# ATmega324PB_Xplained_Pro_Target_MCU.net
KiCad netlist of a schematic drawn in Altium Designer
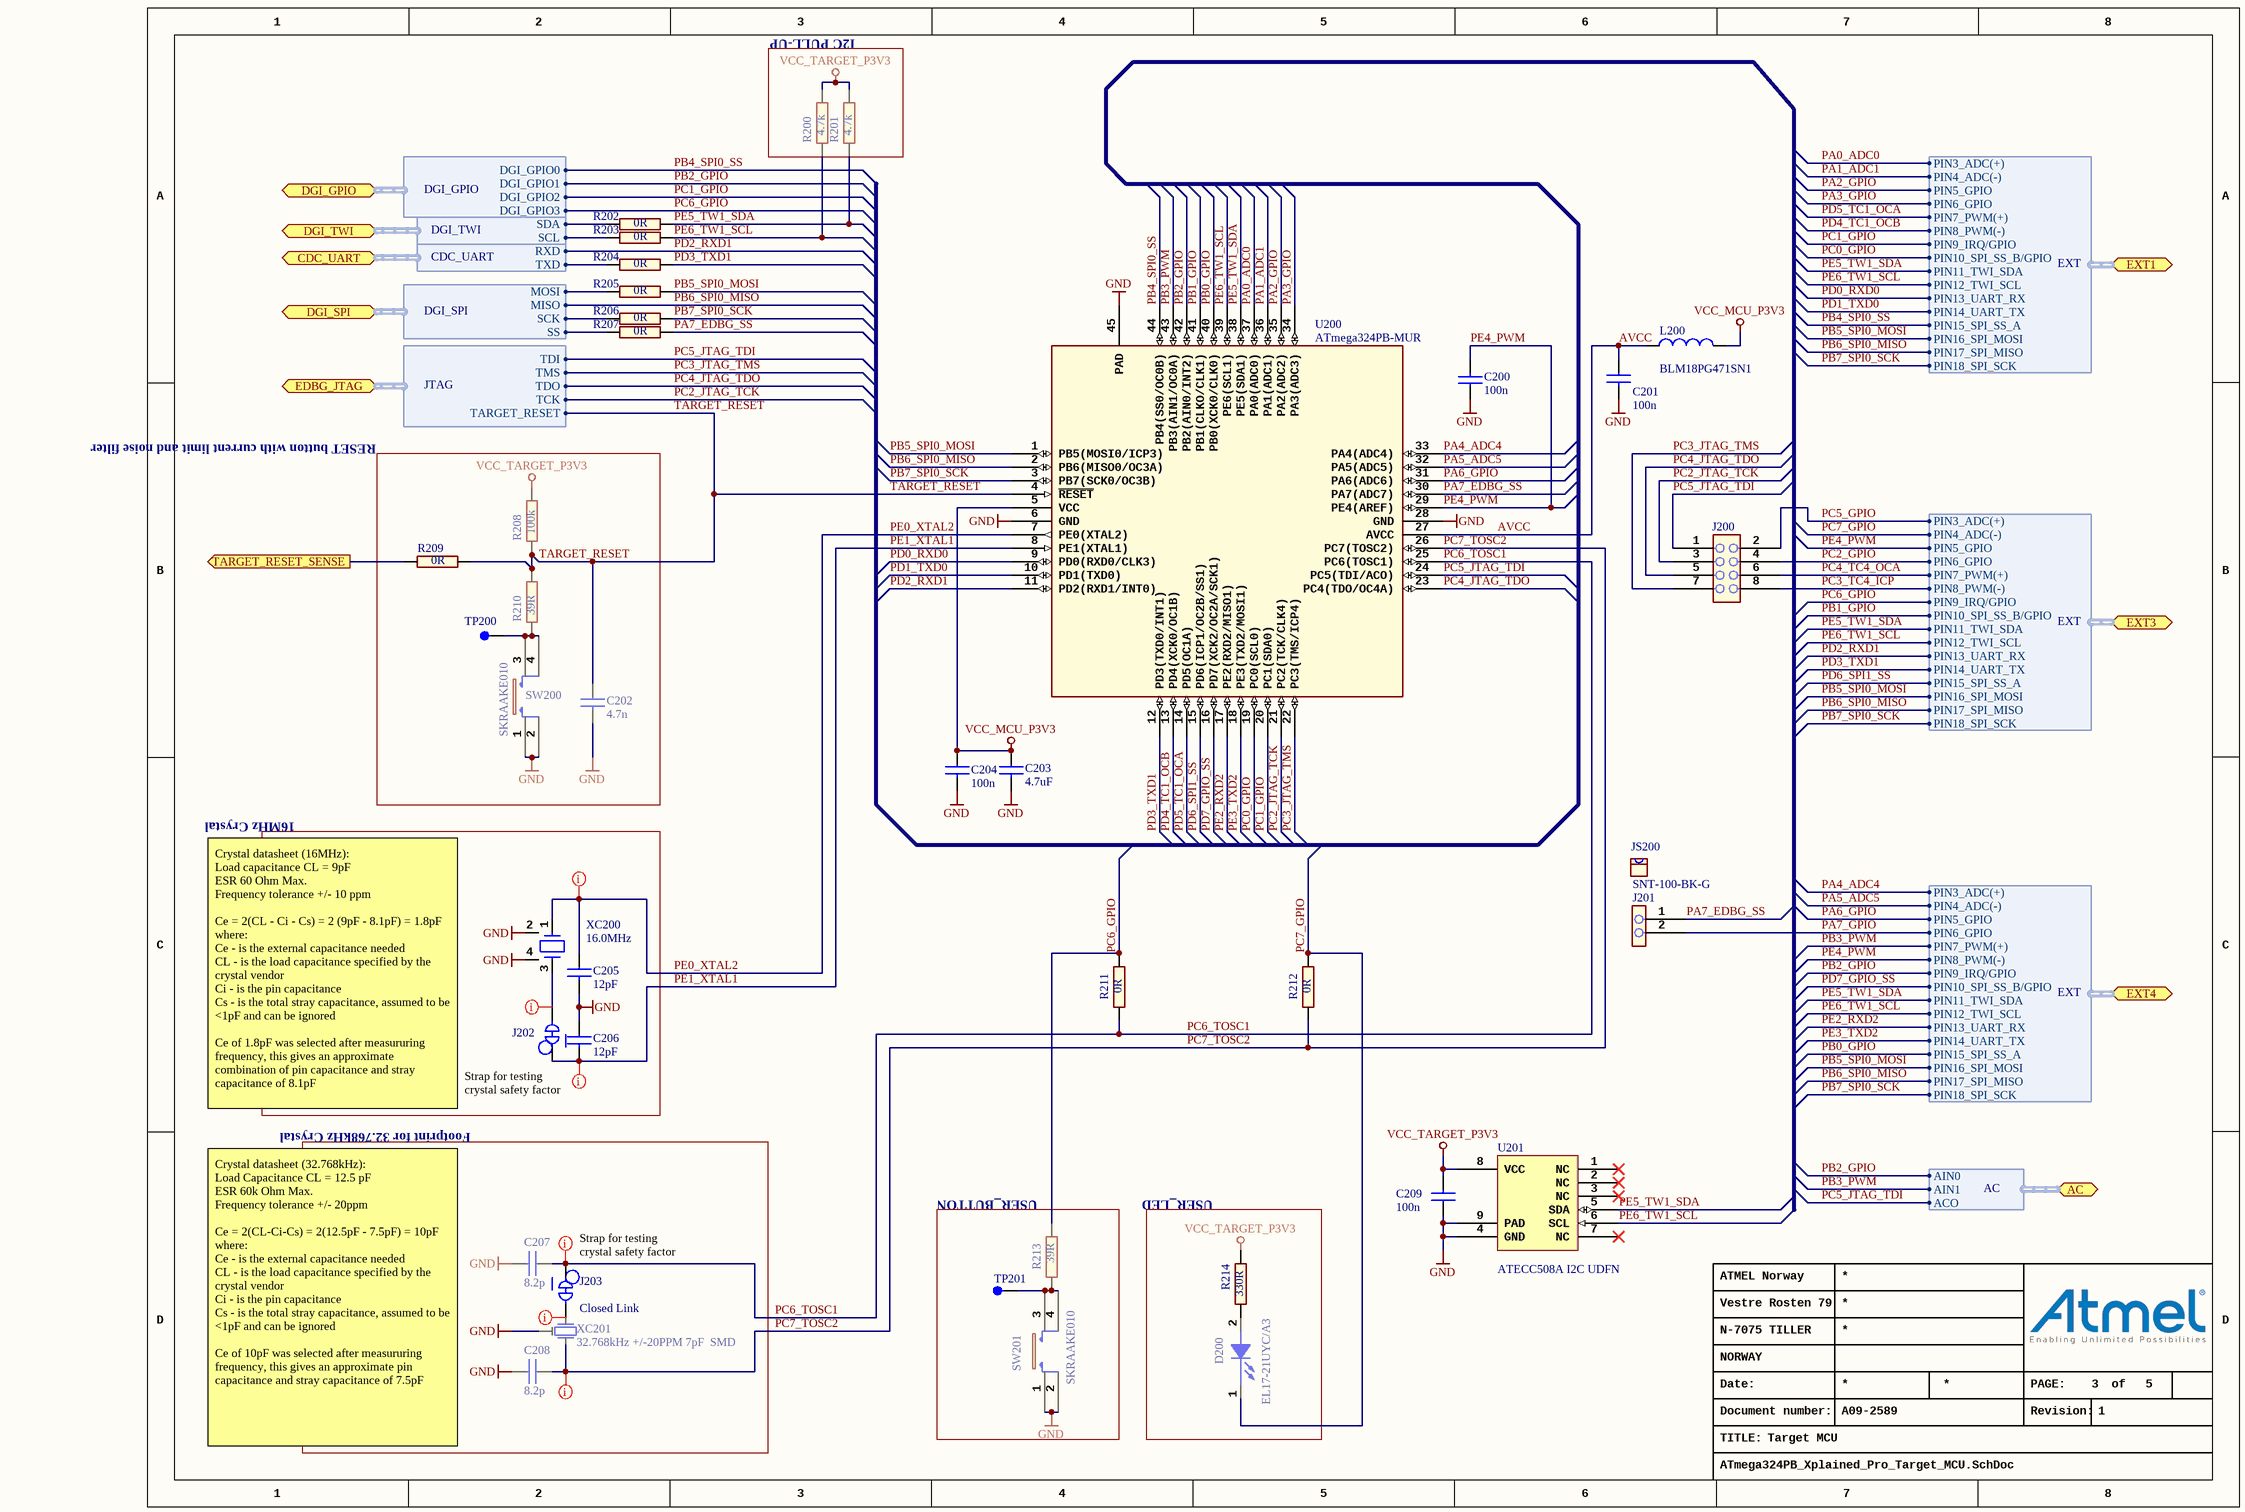
[diagram p0: ATmega324PB_Xplained_Pro_Target_MCU.SchDoc]

(export (version "E")
  (design (tool "Eeschema 10.0.6"))
  (components
    (comp (ref "C200")
      (value "100n")
      (footprint "AP1-00001")
      (description "Ceramic capacitor, SMD 0402, X7R, 16V, +/-10%")
      (fields (field (name "TOLERANCE") "16V, +/-10%") (field (name "MANUFACTURER") "Kemet"))
      (libsource (lib "AltiumDbLib") (part "CAP-NONPOL"))
    )
    (comp (ref "C201")
      (value "100n")
      (footprint "AP1-00001")
      (description "Ceramic capacitor, SMD 0402, X7R, 16V, +/-10%")
      (fields (field (name "TOLERANCE") "16V, +/-10%") (field (name "MANUFACTURER") "Kemet"))
      (libsource (lib "AltiumDbLib") (part "CAP-NONPOL"))
    )
    (comp (ref "C202")
      (value "4.7n")
      (footprint "AP1-00053")
      (description "Ceramic capacitor, SMD 0402, X7R, 25V, +/-10% (de35287)")
      (fields (field (name "TOLERANCE") "25V, +/-10%"))
      (libsource (lib "AltiumDbLib") (part "CAP-NONPOL"))
    )
    (comp (ref "C203")
      (value "4.7uF")
      (footprint "AP1-00039")
      (description "Ceramic capacitor, SMD 0603, X5R, 10V, 10% (de31036)")
      (fields (field (name "MANUFACTURER") "tdk") (field (name "MPN") "C1608X5R1A475K"))
      (libsource (lib "AltiumDbLib") (part "CAP-NONPOL"))
    )
    (comp (ref "C204")
      (value "100n")
      (footprint "AP1-00001")
      (description "Ceramic capacitor, SMD 0402, X7R, 16V, +/-10%")
      (fields (field (name "TOLERANCE") "16V, +/-10%") (field (name "MANUFACTURER") "Kemet"))
      (libsource (lib "AltiumDbLib") (part "CAP-NONPOL"))
    )
    (comp (ref "C205")
      (value "12pF")
      (footprint "AP1-00038")
      (description "Ceramic capacitor, SMD 0402, NP0, 50V, +/-5% (de19819)")
      (fields (field (name "TOLERANCE") "5%") (field (name "MANUFACTURER") "Kyocera-elco"))
      (libsource (lib "AltiumDbLib") (part "CAP-NONPOL"))
    )
    (comp (ref "C206")
      (value "12pF")
      (footprint "AP1-00038")
      (description "Ceramic capacitor, SMD 0402, NP0, 50V, +/-5% (de19819)")
      (fields (field (name "TOLERANCE") "5%") (field (name "MANUFACTURER") "Kyocera-elco"))
      (libsource (lib "AltiumDbLib") (part "CAP-NONPOL"))
    )
    (comp (ref "C207")
      (value "8.2p")
      (footprint "AP1-00001")
      (description "Ceramic capacitor, SMD 0402, NP0, 50V, +/-5%")
      (fields (field (name "TOLERANCE") "50V, +/-5%"))
      (libsource (lib "AltiumDbLib") (part "CAP-NONPOL"))
    )
    (comp (ref "C208")
      (value "8.2p")
      (footprint "AP1-00001")
      (description "Ceramic capacitor, SMD 0402, NP0, 50V, +/-5%")
      (fields (field (name "TOLERANCE") "50V, +/-5%"))
      (libsource (lib "AltiumDbLib") (part "CAP-NONPOL"))
    )
    (comp (ref "C209")
      (value "100n")
      (footprint "AP1-00001")
      (description "Ceramic capacitor, SMD 0402, X7R, 16V, +/-10%")
      (fields (field (name "TOLERANCE") "16V, +/-10%") (field (name "MANUFACTURER") "Kemet"))
      (libsource (lib "AltiumDbLib") (part "CAP-NONPOL"))
    )
    (comp (ref "D200")
      (value "EL17-21UYC/A3")
      (footprint "AP4-00013")
      (description "LED, Yellow, Wave length=591nm, SMD 0805, ±70°")
      (fields (field (name "MANUFACTURER") "Everlight") (field (name "MPN") "17-21UYC/S530-A3/TR8"))
      (libsource (lib "AltiumDbLib") (part "LED_12"))
    )
    (comp (ref "J200")
      (value "~")
      (footprint "AP8-00971")
      (description "2x4 pin header, 2.54 mm pitch, Pin-in-Paste THM")
      (fields (field (name "MANUFACTURER") "SAMTEC") (field (name "MPN") "HMTSW-104-23-F-D-237"))
      (libsource (lib "AltiumDbLib") (part "HEADER 2x4"))
    )
    (comp (ref "J201")
      (value "~")
      (footprint "AP8-00733")
      (description "1x2 pin header, 2.54mm pitch, Pin-in-Paste THM")
      (fields (field (name "MANUFACTURER") "SAMTEC") (field (name "MPN") "HMTSW-102-23-F-S-237"))
      (libsource (lib "AltiumDbLib") (part "HEADER 1x2"))
    )
    (comp (ref "J202")
      (value "~")
      (footprint "AP8-00595")
      (description "Closed Link 0402")
      (libsource (lib "AltiumDbLib") (part "SMD-STRAP_CLOSED"))
    )
    (comp (ref "J203")
      (value "Closed Link")
      (footprint "AP8-00595")
      (description "Closed Link 0402")
      (libsource (lib "AltiumDbLib") (part "SMD-STRAP_CLOSED"))
    )
    (comp (ref "JS200")
      (value "SNT-100-BK-G")
      (footprint "AP8-00525")
      (description "Jumper cap for 2.54mm pinheader")
      (fields (field (name "MANUFACTURER") "SAMTEC"))
      (libsource (lib "AltiumDbLib") (part "JUMPER_CAP"))
    )
    (comp (ref "L200")
      (value "BLM18PG471SN1")
      (footprint "AP3-00005")
      (description "SMD RF inductor 0603. Z=470Ohm (@100MHz), Max R(dc)=0.65Ohm, Max current=1A")
      (fields (field (name "TOLERANCE") "±25%") (field (name "MANUFACTURER") "Murata"))
      (libsource (lib "AltiumDbLib") (part "INDUCTOR"))
    )
    (comp (ref "R200")
      (value "4.7k")
      (footprint "AP2-00000")
      (description "Thick film resistor, SMD 0402, 1/16W, 1%")
      (fields (field (name "TOLERANCE") "1 %"))
      (libsource (lib "") (part "R2_1"))
    )
    (comp (ref "R201")
      (value "4.7k")
      (footprint "AP2-00000")
      (description "Thick film resistor, SMD 0402, 1/16W, 1%")
      (fields (field (name "TOLERANCE") "1 %"))
      (libsource (lib "") (part "R2_1"))
    )
    (comp (ref "R202")
      (value "0R")
      (footprint "AP2-00000")
      (description "RES 0.0 OHM 1/16W 0402 SMD")
      (fields (field (name "TOLERANCE") "1 %") (field (name "MANUFACTURER") "(n/a)"))
      (libsource (lib "AltiumDbLib") (part "R2"))
    )
    (comp (ref "R203")
      (value "0R")
      (footprint "AP2-00000")
      (description "RES 0.0 OHM 1/16W 0402 SMD")
      (fields (field (name "TOLERANCE") "1 %") (field (name "MANUFACTURER") "(n/a)"))
      (libsource (lib "AltiumDbLib") (part "R2"))
    )
    (comp (ref "R204")
      (value "0R")
      (footprint "AP2-00000")
      (description "RES 0.0 OHM 1/16W 0402 SMD")
      (fields (field (name "TOLERANCE") "1 %") (field (name "MANUFACTURER") "(n/a)"))
      (libsource (lib "AltiumDbLib") (part "R2"))
    )
    (comp (ref "R205")
      (value "0R")
      (footprint "AP2-00000")
      (description "RES 0.0 OHM 1/16W 0402 SMD")
      (fields (field (name "TOLERANCE") "1 %") (field (name "MANUFACTURER") "(n/a)"))
      (libsource (lib "AltiumDbLib") (part "R2"))
    )
    (comp (ref "R206")
      (value "0R")
      (footprint "AP2-00000")
      (description "RES 0.0 OHM 1/16W 0402 SMD")
      (fields (field (name "TOLERANCE") "1 %") (field (name "MANUFACTURER") "(n/a)"))
      (libsource (lib "AltiumDbLib") (part "R2"))
    )
    (comp (ref "R207")
      (value "0R")
      (footprint "AP2-00000")
      (description "RES 0.0 OHM 1/16W 0402 SMD")
      (fields (field (name "TOLERANCE") "1 %") (field (name "MANUFACTURER") "(n/a)"))
      (libsource (lib "AltiumDbLib") (part "R2"))
    )
    (comp (ref "R208")
      (value "100k")
      (footprint "AP2-00011")
      (description "Thick film resistor, SMD 0402, 1/16W, 1%")
      (fields (field (name "TOLERANCE") "1 %"))
      (libsource (lib "") (part "R2_1"))
    )
    (comp (ref "R209")
      (value "0R")
      (footprint "AP2-00000")
      (description "RES 0.0 OHM 1/16W 0402 SMD")
      (fields (field (name "TOLERANCE") "1 %") (field (name "MANUFACTURER") "(n/a)"))
      (libsource (lib "AltiumDbLib") (part "R2"))
    )
    (comp (ref "R210")
      (value "39R")
      (footprint "AP2-00011")
      (description "Thick film resistor, SMD 0402, 1/16W, 1%")
      (fields (field (name "TOLERANCE") "1 %"))
      (libsource (lib "") (part "R2_2"))
    )
    (comp (ref "R211")
      (value "0R")
      (footprint "AP2-00000")
      (description "RES 0.0 OHM 1/16W 0402 SMD")
      (fields (field (name "TOLERANCE") "1 %") (field (name "MANUFACTURER") "(n/a)"))
      (libsource (lib "") (part "R2_1"))
    )
    (comp (ref "R212")
      (value "0R")
      (footprint "AP2-00000")
      (description "RES 0.0 OHM 1/16W 0402 SMD")
      (fields (field (name "TOLERANCE") "1 %") (field (name "MANUFACTURER") "(n/a)"))
      (libsource (lib "") (part "R2_1"))
    )
    (comp (ref "R213")
      (value "39R")
      (footprint "AP2-00011")
      (description "Thick film resistor, SMD 0402, 1/16W, 1%")
      (fields (field (name "TOLERANCE") "1 %"))
      (libsource (lib "") (part "R2_2"))
    )
    (comp (ref "R214")
      (value "330R")
      (footprint "AP2-00000")
      (description "Thick film resistor, SMD 0402, 1/16W, 1%")
      (fields (field (name "TOLERANCE") "1 %"))
      (libsource (lib "") (part "R2_1"))
    )
    (comp (ref "SW200")
      (value "SKRAAKE010")
      (footprint "AP8-00137")
      (description "6.2x6.2 mm SMD tact switch, same as A08-0091 but less force is needed")
      (fields
        (field (name "MANUFACTURER") "ALPS")
        (field (name "Comment") "Can be ordered in low volumes from Mouser")
      )
      (libsource (lib "AltiumDbLib") (part "PUSHBUTTON1"))
    )
    (comp (ref "SW201")
      (value "SKRAAKE010")
      (footprint "AP8-00137")
      (description "6.2x6.2 mm SMD tact switch, same as A08-0091 but less force is needed")
      (fields
        (field (name "MANUFACTURER") "ALPS")
        (field (name "Comment") "Can be ordered in low volumes from Mouser")
      )
      (libsource (lib "AltiumDbLib") (part "PUSHBUTTON1"))
    )
    (comp (ref "TP200")
      (value "~")
      (footprint "AP8-00010")
      (description "Single SMD testpad")
      (libsource (lib "AltiumDbLib") (part "TESTPOINT"))
    )
    (comp (ref "TP201")
      (value "~")
      (footprint "AP8-00010")
      (description "Single SMD testpad")
      (libsource (lib "AltiumDbLib") (part "TESTPOINT"))
    )
    (comp (ref "U200")
      (value "ATmega324PB-MUR")
      (footprint "AP6-00147")
      (description "AVR 8-bit RISC MCU")
      (fields
        (field (name "MANUFACTURER") "ATMEL")
        (field (name "Comment") "Footprint has tight silkscreen to solder mask expansion clearance")
      )
      (libsource (lib "AltiumDbLib") (part "ATmega324PB"))
    )
    (comp (ref "U201")
      (value "ATECC508A I2C UDFN")
      (footprint "AP6-00409")
      (description "ATECC508A with an I2C Interface and a 8 Pin UDFN Package with Paddle")
      (fields (field (name "MANUFACTURER") "ATMEL") (field (name "MPN") "ATECC508A-MAHDA-T"))
      (libsource (lib "AltiumDbLib") (part "ATECC508A_I2C_UDFN"))
    )
    (comp (ref "XC200")
      (value "16.0MHz")
      (footprint "AP7-00061")
      (description "16MHz uXtal, 3.2 x 2.5 mm SMD, CL=9pF, 15PPM, ESR=80ohm(Max.")
      (fields (field (name "TOLERANCE") "15ppm") (field (name "MANUFACTURER") "Epson Toyocom"))
      (libsource (lib "AltiumDbLib") (part "TSX-3225"))
    )
    (comp (ref "XC201")
      (value "32.768kHz +/-20PPM 7pF  SMD")
      (footprint "AP7-00044")
      (description "32k768 crystal, +-20ppm, CL=7pF, max ESR 60kOhm, SMD")
      (fields (field (name "TOLERANCE") "+/- 20 PPM") (field (name "MANUFACTURER") "Micro Crystal"))
      (libsource (lib "AltiumDbLib") (part "CRYSTAL_2P_metal"))
    )
  )
  (nets
    (net (code "7") (name "/AVCC") (class "Default")
      (node (ref "C201") (pin "1") (pinfunction "1_1") (pintype "passive"))
      (node (ref "L200") (pin "1") (pinfunction "1_1") (pintype "passive"))
      (node (ref "U200") (pin "27") (pinfunction "AVCC_27") (pintype "power_in"))
    )
    (net (code "9") (name "/MOSI") (class "Default")
      (node (ref "R205") (pin "1") (pinfunction "1_1") (pintype "passive"))
    )
    (net (code "10") (name "/PA0_ADC0") (class "Default")
      (node (ref "U200") (pin "37") (pinfunction "PA0(ADC0)_37") (pintype "bidirectional"))
    )
    (net (code "11") (name "/PA1_ADC1") (class "Default")
      (node (ref "U200") (pin "36") (pinfunction "PA1(ADC1)_36") (pintype "bidirectional"))
    )
    (net (code "12") (name "/PA2_GPIO") (class "Default")
      (node (ref "U200") (pin "35") (pinfunction "PA2(ADC2)_35") (pintype "bidirectional"))
    )
    (net (code "13") (name "/PA3_GPIO") (class "Default")
      (node (ref "U200") (pin "34") (pinfunction "PA3(ADC3)_34") (pintype "bidirectional"))
    )
    (net (code "14") (name "/PA4_ADC4") (class "Default")
      (node (ref "U200") (pin "33") (pinfunction "PA4(ADC4)_33") (pintype "bidirectional"))
    )
    (net (code "15") (name "/PA5_ADC5") (class "Default")
      (node (ref "U200") (pin "32") (pinfunction "PA5(ADC5)_32") (pintype "bidirectional"))
    )
    (net (code "16") (name "/PA6_GPIO") (class "Default")
      (node (ref "U200") (pin "31") (pinfunction "PA6(ADC6)_31") (pintype "bidirectional"))
    )
    (net (code "17") (name "/PA7_EDBG_SS") (class "Default")
      (node (ref "J201") (pin "1") (pinfunction "1_1") (pintype "passive"))
      (node (ref "R207") (pin "2") (pinfunction "2_2") (pintype "passive"))
      (node (ref "U200") (pin "30") (pinfunction "PA7(ADC7)_30") (pintype "bidirectional"))
    )
    (net (code "18") (name "/PA7_GPIO") (class "Default")
      (node (ref "J201") (pin "2") (pinfunction "2_2") (pintype "passive"))
    )
    (net (code "19") (name "/PB0_GPIO") (class "Default")
      (node (ref "U200") (pin "40") (pinfunction "PB0(XCK0/CLK0)_40") (pintype "bidirectional"))
    )
    (net (code "20") (name "/PB1_GPIO") (class "Default")
      (node (ref "U200") (pin "41") (pinfunction "PB1(CLKO/CLK1)_41") (pintype "bidirectional"))
    )
    (net (code "21") (name "/PB2_GPIO") (class "Default")
      (node (ref "U200") (pin "42") (pinfunction "PB2(AIN0/INT2)_42") (pintype "bidirectional"))
    )
    (net (code "22") (name "/PB3_PWM") (class "Default")
      (node (ref "U200") (pin "43") (pinfunction "PB3(AIN1/OC0A)_43") (pintype "bidirectional"))
    )
    (net (code "23") (name "/PB4_SPI0_SS") (class "Default")
      (node (ref "U200") (pin "44") (pinfunction "PB4(SS0/OC0B)_44") (pintype "bidirectional"))
    )
    (net (code "24") (name "/PB5_SPI0_MOSI") (class "Default")
      (node (ref "R205") (pin "2") (pinfunction "2_2") (pintype "passive"))
      (node (ref "U200") (pin "1") (pinfunction "PB5(MOSI0/ICP3)_1") (pintype "bidirectional"))
    )
    (net (code "25") (name "/PB6_SPI0_MISO") (class "Default")
      (node (ref "U200") (pin "2") (pinfunction "PB6(MISO0/OC3A)_2") (pintype "bidirectional"))
    )
    (net (code "26") (name "/PB7_SPI0_SCK") (class "Default")
      (node (ref "R206") (pin "2") (pinfunction "2_2") (pintype "passive"))
      (node (ref "U200") (pin "3") (pinfunction "PB7(SCK0/OC3B)_3") (pintype "bidirectional"))
    )
    (net (code "27") (name "/PC0_GPIO") (class "Default")
      (node (ref "U200") (pin "19") (pinfunction "PC0(SCL0)_19") (pintype "bidirectional"))
    )
    (net (code "28") (name "/PC1_GPIO") (class "Default")
      (node (ref "U200") (pin "20") (pinfunction "PC1(SDA0)_20") (pintype "bidirectional"))
    )
    (net (code "29") (name "/PC2_GPIO") (class "Default")
      (node (ref "J200") (pin "4") (pinfunction "4_4") (pintype "passive"))
    )
    (net (code "30") (name "/PC2_JTAG_TCK") (class "Default")
      (node (ref "J200") (pin "3") (pinfunction "3_3") (pintype "passive"))
      (node (ref "U200") (pin "21") (pinfunction "PC2(TCK/CLK4)_21") (pintype "bidirectional"))
    )
    (net (code "31") (name "/PC3_JTAG_TMS") (class "Default")
      (node (ref "J200") (pin "7") (pinfunction "7_7") (pintype "passive"))
      (node (ref "U200") (pin "22") (pinfunction "PC3(TMS/ICP4)_22") (pintype "bidirectional"))
    )
    (net (code "32") (name "/PC3_TC4_ICP") (class "Default")
      (node (ref "J200") (pin "8") (pinfunction "8_8") (pintype "passive"))
    )
    (net (code "33") (name "/PC4_JTAG_TDO") (class "Default")
      (node (ref "J200") (pin "5") (pinfunction "5_5") (pintype "passive"))
      (node (ref "U200") (pin "23") (pinfunction "PC4(TDO/OC4A)_23") (pintype "bidirectional"))
    )
    (net (code "34") (name "/PC4_TC4_OCA") (class "Default")
      (node (ref "J200") (pin "6") (pinfunction "6_6") (pintype "passive"))
    )
    (net (code "35") (name "/PC5_GPIO") (class "Default")
      (node (ref "J200") (pin "2") (pinfunction "2_2") (pintype "passive"))
    )
    (net (code "36") (name "/PC5_JTAG_TDI") (class "Default")
      (node (ref "J200") (pin "1") (pinfunction "1_1") (pintype "passive"))
      (node (ref "U200") (pin "24") (pinfunction "PC5(TDI/ACO)_24") (pintype "bidirectional"))
    )
    (net (code "37") (name "/PC6_GPIO") (class "Default")
      (node (ref "R211") (pin "2") (pinfunction "2_2") (pintype "passive"))
      (node (ref "R213") (pin "2") (pinfunction "2_2") (pintype "passive"))
    )
    (net (code "38") (name "/PC6_TOSC1") (class "Default")
      (node (ref "C207") (pin "1") (pinfunction "1_1") (pintype "passive"))
      (node (ref "J203") (pin "1") (pinfunction "1_1") (pintype "passive"))
      (node (ref "R211") (pin "1") (pinfunction "1_1") (pintype "passive"))
      (node (ref "U200") (pin "25") (pinfunction "PC6(TOSC1)_25") (pintype "bidirectional"))
    )
    (net (code "39") (name "/PC7_GPIO") (class "Default")
      (node (ref "D200") (pin "1") (pinfunction "CATHODE_1") (pintype "passive"))
      (node (ref "R212") (pin "2") (pinfunction "2_2") (pintype "passive"))
    )
    (net (code "40") (name "/PC7_TOSC2") (class "Default")
      (node (ref "C208") (pin "1") (pinfunction "1_1") (pintype "passive"))
      (node (ref "R212") (pin "1") (pinfunction "1_1") (pintype "passive"))
      (node (ref "U200") (pin "26") (pinfunction "PC7(TOSC2)_26") (pintype "bidirectional"))
      (node (ref "XC201") (pin "1") (pinfunction "1_1") (pintype "passive"))
    )
    (net (code "41") (name "/PD0_RXD0") (class "Default")
      (node (ref "U200") (pin "9") (pinfunction "PD0(RXD0/CLK3)_9") (pintype "bidirectional"))
    )
    (net (code "42") (name "/PD1_TXD0") (class "Default")
      (node (ref "U200") (pin "10") (pinfunction "PD1(TXD0)_10") (pintype "bidirectional"))
    )
    (net (code "43") (name "/PD2_RXD1") (class "Default")
      (node (ref "U200") (pin "11") (pinfunction "PD2(RXD1/INT0)_11") (pintype "bidirectional"))
    )
    (net (code "44") (name "/PD3_TXD1") (class "Default")
      (node (ref "R204") (pin "2") (pinfunction "2_2") (pintype "passive"))
      (node (ref "U200") (pin "12") (pinfunction "PD3(TXD0/INT1)_12") (pintype "bidirectional"))
    )
    (net (code "45") (name "/PD4_TC1_OCB") (class "Default")
      (node (ref "U200") (pin "13") (pinfunction "PD4(XCK0/OC1B)_13") (pintype "bidirectional"))
    )
    (net (code "46") (name "/PD5_TC1_OCA") (class "Default")
      (node (ref "U200") (pin "14") (pinfunction "PD5(OC1A)_14") (pintype "bidirectional"))
    )
    (net (code "47") (name "/PD6_SPI1_SS") (class "Default")
      (node (ref "U200") (pin "15") (pinfunction "PD6(ICP1/OC2B/SS1)_15") (pintype "bidirectional"))
    )
    (net (code "48") (name "/PD7_GPIO_SS") (class "Default")
      (node (ref "U200") (pin "16") (pinfunction "PD7(XCK2/OC2A/SCK1)_16") (pintype "bidirectional"))
    )
    (net (code "49") (name "/PE0_XTAL2") (class "Default")
      (node (ref "C205") (pin "1") (pinfunction "1_1") (pintype "passive"))
      (node (ref "U200") (pin "7") (pinfunction "PE0(XTAL2)_7") (pintype "output"))
      (node (ref "XC200") (pin "1") (pinfunction "IN_1") (pintype "passive"))
    )
    (net (code "50") (name "/PE1_XTAL1") (class "Default")
      (node (ref "C206") (pin "2") (pinfunction "2_2") (pintype "passive"))
      (node (ref "J202") (pin "1") (pinfunction "1_1") (pintype "passive"))
      (node (ref "U200") (pin "8") (pinfunction "PE1(XTAL1)_8") (pintype "input"))
    )
    (net (code "51") (name "/PE2_RXD2") (class "Default")
      (node (ref "U200") (pin "17") (pinfunction "PE2(RXD2/MISO1)_17") (pintype "bidirectional"))
    )
    (net (code "52") (name "/PE3_TXD2") (class "Default")
      (node (ref "U200") (pin "18") (pinfunction "PE3(TXD2/MOSI1)_18") (pintype "bidirectional"))
    )
    (net (code "53") (name "/PE4_PWM") (class "Default")
      (node (ref "C200") (pin "2") (pinfunction "2_2") (pintype "passive"))
      (node (ref "U200") (pin "29") (pinfunction "PE4(AREF)_29") (pintype "bidirectional"))
    )
    (net (code "54") (name "/PE5_TW1_SDA") (class "Default")
      (node (ref "R201") (pin "1") (pinfunction "1_1") (pintype "passive"))
      (node (ref "R202") (pin "2") (pinfunction "2_2") (pintype "passive"))
      (node (ref "U200") (pin "38") (pinfunction "PE5(SDA1)_38") (pintype "bidirectional"))
      (node (ref "U201") (pin "5") (pinfunction "SDA_5") (pintype "bidirectional"))
    )
    (net (code "55") (name "/PE6_TW1_SCL") (class "Default")
      (node (ref "R200") (pin "1") (pinfunction "1_1") (pintype "passive"))
      (node (ref "R203") (pin "2") (pinfunction "2_2") (pintype "passive"))
      (node (ref "U200") (pin "39") (pinfunction "PE6(SCL1)_39") (pintype "bidirectional"))
      (node (ref "U201") (pin "6") (pinfunction "SCL_6") (pintype "input"))
    )
    (net (code "56") (name "/SCK") (class "Default")
      (node (ref "R206") (pin "1") (pinfunction "1_1") (pintype "passive"))
    )
    (net (code "57") (name "/SCL") (class "Default")
      (node (ref "R203") (pin "1") (pinfunction "1_1") (pintype "passive"))
    )
    (net (code "58") (name "/SDA") (class "Default")
      (node (ref "R202") (pin "1") (pinfunction "1_1") (pintype "passive"))
    )
    (net (code "59") (name "/SS") (class "Default")
      (node (ref "R207") (pin "1") (pinfunction "1_1") (pintype "passive"))
    )
    (net (code "60") (name "/TARGET_RESET") (class "Default")
      (node (ref "C202") (pin "1") (pinfunction "1_1") (pintype "passive"))
      (node (ref "R208") (pin "1") (pinfunction "1_1") (pintype "passive"))
      (node (ref "R209") (pin "2") (pinfunction "2_2") (pintype "passive"))
      (node (ref "R210") (pin "2") (pinfunction "2_2") (pintype "passive"))
      (node (ref "U200") (pin "4") (pinfunction "~{RESET}_4") (pintype "input"))
    )
    (net (code "61") (name "/TARGET_RESET_SENSE") (class "Default")
      (node (ref "R209") (pin "1") (pinfunction "1_1") (pintype "passive"))
    )
    (net (code "62") (name "/TXD") (class "Default")
      (node (ref "R204") (pin "1") (pinfunction "1_1") (pintype "passive"))
    )
    (net (code "68") (name "GND") (class "Default")
      (node (ref "C200") (pin "1") (pinfunction "1_1") (pintype "passive"))
      (node (ref "C201") (pin "2") (pinfunction "2_2") (pintype "passive"))
      (node (ref "C202") (pin "2") (pinfunction "2_2") (pintype "passive"))
      (node (ref "C203") (pin "2") (pinfunction "2_2") (pintype "passive"))
      (node (ref "C204") (pin "2") (pinfunction "2_2") (pintype "passive"))
      (node (ref "C205") (pin "2") (pinfunction "2_2") (pintype "passive"))
      (node (ref "C206") (pin "1") (pinfunction "1_1") (pintype "passive"))
      (node (ref "C207") (pin "2") (pinfunction "2_2") (pintype "passive"))
      (node (ref "C208") (pin "2") (pinfunction "2_2") (pintype "passive"))
      (node (ref "C209") (pin "1") (pinfunction "1_1") (pintype "passive"))
      (node (ref "SW200") (pin "1") (pinfunction "1_1") (pintype "passive"))
      (node (ref "SW200") (pin "2") (pinfunction "2_2") (pintype "passive"))
      (node (ref "SW201") (pin "1") (pinfunction "1_1") (pintype "passive"))
      (node (ref "SW201") (pin "2") (pinfunction "2_2") (pintype "passive"))
      (node (ref "U200") (pin "28") (pinfunction "GND_28") (pintype "power_in"))
      (node (ref "U200") (pin "45") (pinfunction "PAD_45") (pintype "power_in"))
      (node (ref "U200") (pin "6") (pinfunction "GND_6") (pintype "power_in"))
      (node (ref "U201") (pin "4") (pinfunction "GND_4") (pintype "power_in"))
      (node (ref "U201") (pin "9") (pinfunction "PAD_9") (pintype "power_in"))
      (node (ref "XC200") (pin "2") (pinfunction "GND_2") (pintype "passive"))
      (node (ref "XC200") (pin "4") (pinfunction "GND_4") (pintype "passive"))
      (node (ref "XC201") (pin "3") (pinfunction "3_3") (pintype "passive"))
    )
    (net (code "69") (name "Net-(D200-ANODE)") (class "Default")
      (node (ref "D200") (pin "2") (pinfunction "ANODE_2") (pintype "passive"))
      (node (ref "R214") (pin "1") (pinfunction "1_1") (pintype "passive"))
    )
    (net (code "70") (name "Net-(J203-Pad2)") (class "Default")
      (node (ref "J203") (pin "2") (pinfunction "2_2") (pintype "passive"))
      (node (ref "XC201") (pin "2") (pinfunction "2_2") (pintype "passive"))
    )
    (net (code "71") (name "Net-(R210-Pad1)") (class "Default")
      (node (ref "R210") (pin "1") (pinfunction "1_1") (pintype "passive"))
      (node (ref "SW200") (pin "3") (pinfunction "3_3") (pintype "passive"))
      (node (ref "SW200") (pin "4") (pinfunction "4_4") (pintype "passive"))
      (node (ref "TP200") (pin "1") (pinfunction "1_1") (pintype "passive"))
    )
    (net (code "72") (name "Net-(R213-Pad1)") (class "Default")
      (node (ref "R213") (pin "1") (pinfunction "1_1") (pintype "passive"))
      (node (ref "SW201") (pin "3") (pinfunction "3_3") (pintype "passive"))
      (node (ref "SW201") (pin "4") (pinfunction "4_4") (pintype "passive"))
      (node (ref "TP201") (pin "1") (pinfunction "1_1") (pintype "passive"))
    )
    (net (code "73") (name "Net-(XC200-OUT)") (class "Default")
      (node (ref "J202") (pin "2") (pinfunction "2_2") (pintype "passive"))
      (node (ref "XC200") (pin "3") (pinfunction "OUT_3") (pintype "passive"))
    )
    (net (code "74") (name "VCC_MCU_P3V3") (class "Default")
      (node (ref "C203") (pin "1") (pinfunction "1_1") (pintype "passive"))
      (node (ref "C204") (pin "1") (pinfunction "1_1") (pintype "passive"))
      (node (ref "L200") (pin "2") (pinfunction "2_2") (pintype "passive"))
      (node (ref "U200") (pin "5") (pinfunction "VCC_5") (pintype "power_in"))
    )
    (net (code "75") (name "VCC_TARGET_P3V3") (class "Default")
      (node (ref "C209") (pin "2") (pinfunction "2_2") (pintype "passive"))
      (node (ref "R200") (pin "2") (pinfunction "2_2") (pintype "passive"))
      (node (ref "R201") (pin "2") (pinfunction "2_2") (pintype "passive"))
      (node (ref "R208") (pin "2") (pinfunction "2_2") (pintype "passive"))
      (node (ref "R214") (pin "2") (pinfunction "2_2") (pintype "passive"))
      (node (ref "U201") (pin "8") (pinfunction "VCC_8") (pintype "power_in"))
    )
    (net (code "76") (name "unconnected-(U201-NC-Pad1)") (class "Default")
      (node (ref "U201") (pin "1") (pinfunction "NC_1") (pintype "passive+no_connect"))
    )
    (net (code "77") (name "unconnected-(U201-NC-Pad2)") (class "Default")
      (node (ref "U201") (pin "2") (pinfunction "NC_2") (pintype "passive+no_connect"))
    )
    (net (code "78") (name "unconnected-(U201-NC-Pad3)") (class "Default")
      (node (ref "U201") (pin "3") (pinfunction "NC_3") (pintype "passive+no_connect"))
    )
    (net (code "79") (name "unconnected-(U201-NC-Pad7)") (class "Default")
      (node (ref "U201") (pin "7") (pinfunction "NC_7") (pintype "passive+no_connect"))
    )
  )
)
